# BoostConverter.net
KiCad netlist of a schematic drawn in Altium Designer
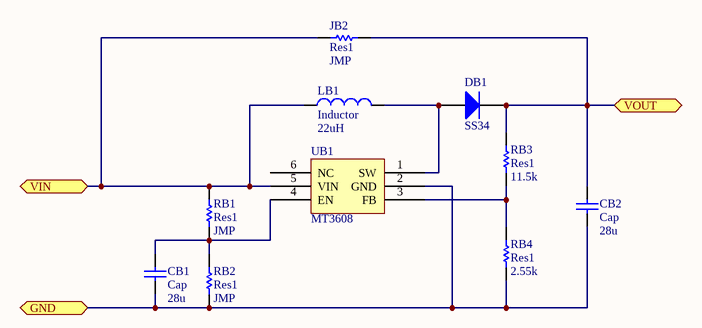
[diagram p0: BoostConverter.SchDoc]

(export (version "E")
  (design (tool "Eeschema 10.0.6"))
  (components
    (comp (ref "CB1")
      (value "Cap")
      (footprint "CAP0603R")
      (description "Capacitor")
      (fields (field (name "ALTIUM_VALUE") "28u") (field (name "PUBLISHER") "Altium Limited"))
      (libsource (lib "Standard") (part "Cap"))
    )
    (comp (ref "CB2")
      (value "Cap")
      (footprint "CAP0603R")
      (description "Capacitor")
      (fields (field (name "ALTIUM_VALUE") "28u") (field (name "PUBLISHER") "Altium Limited"))
      (libsource (lib "Standard") (part "Cap"))
    )
    (comp (ref "DB1")
      (value "SS34")
      (footprint "DO-214AC")
      (description "Default Diode")
      (fields (field (name "PUBLISHER") "Altium Limited"))
      (libsource (lib "Miscellaneous Devices") (part "Diode"))
    )
    (comp (ref "JB2")
      (value "Res1")
      (footprint "RES0603R")
      (description "Resistor")
      (fields (field (name "ALTIUM_VALUE") "JMP") (field (name "PUBLISHER") "Altium Limited"))
      (libsource (lib "Miscellaneous Devices") (part "Res1"))
    )
    (comp (ref "LB1")
      (value "Inductor")
      (footprint "INDUCTOR CD54")
      (fields (field (name "ALTIUM_VALUE") "22uH") (field (name "PUBLISHER") "Altium Limited"))
      (libsource (lib "Standard") (part "Inductor"))
    )
    (comp (ref "RB1")
      (value "Res1")
      (footprint "RES0603R")
      (description "Resistor")
      (fields (field (name "ALTIUM_VALUE") "JMP") (field (name "PUBLISHER") "Altium Limited"))
      (libsource (lib "Miscellaneous Devices") (part "Res1"))
    )
    (comp (ref "RB2")
      (value "Res1")
      (footprint "RES0603R")
      (description "Resistor")
      (fields (field (name "ALTIUM_VALUE") "JMP") (field (name "PUBLISHER") "Altium Limited"))
      (libsource (lib "Miscellaneous Devices") (part "Res1"))
    )
    (comp (ref "RB3")
      (value "Res1")
      (footprint "RES0603R")
      (description "Resistor")
      (fields (field (name "ALTIUM_VALUE") "11.5k") (field (name "PUBLISHER") "Altium Limited"))
      (libsource (lib "Miscellaneous Devices") (part "Res1"))
    )
    (comp (ref "RB4")
      (value "Res1")
      (footprint "RES0603R")
      (description "Resistor")
      (fields (field (name "ALTIUM_VALUE") "2.55k") (field (name "PUBLISHER") "Altium Limited"))
      (libsource (lib "Miscellaneous Devices") (part "Res1"))
    )
    (comp (ref "UB1")
      (value "MT3608")
      (footprint "SOT23-6")
      (description "Boost converter")
      (libsource (lib "IC") (part "MT3608"))
    )
  )
  (nets
    (net (code "1") (name "/GND") (class "Default")
      (node (ref "CB1") (pin "1") (pinfunction "1_1") (pintype "passive"))
      (node (ref "CB2") (pin "1") (pinfunction "1_1") (pintype "passive"))
      (node (ref "RB2") (pin "2") (pinfunction "2_2") (pintype "passive"))
      (node (ref "RB4") (pin "2") (pinfunction "2_2") (pintype "passive"))
      (node (ref "UB1") (pin "2") (pinfunction "GND_2") (pintype "passive"))
    )
    (net (code "2") (name "/VIN") (class "Default")
      (node (ref "JB2") (pin "1") (pinfunction "1_1") (pintype "passive"))
      (node (ref "LB1") (pin "1") (pinfunction "1_1") (pintype "passive"))
      (node (ref "RB1") (pin "1") (pinfunction "1_1") (pintype "passive"))
      (node (ref "UB1") (pin "5") (pinfunction "VIN_5") (pintype "passive"))
    )
    (net (code "3") (name "/VOUT") (class "Default")
      (node (ref "CB2") (pin "2") (pinfunction "2_2") (pintype "passive"))
      (node (ref "DB1") (pin "2") (pinfunction "K_2") (pintype "passive"))
      (node (ref "JB2") (pin "2") (pinfunction "2_2") (pintype "passive"))
      (node (ref "RB3") (pin "1") (pinfunction "1_1") (pintype "passive"))
    )
    (net (code "4") (name "Net-(DB1-A)") (class "Default")
      (node (ref "DB1") (pin "1") (pinfunction "A_1") (pintype "passive"))
      (node (ref "LB1") (pin "2") (pinfunction "2_2") (pintype "passive"))
      (node (ref "UB1") (pin "1") (pinfunction "SW_1") (pintype "passive"))
    )
    (net (code "5") (name "Net-(UB1-EN)") (class "Default")
      (node (ref "CB1") (pin "2") (pinfunction "2_2") (pintype "passive"))
      (node (ref "RB1") (pin "2") (pinfunction "2_2") (pintype "passive"))
      (node (ref "RB2") (pin "1") (pinfunction "1_1") (pintype "passive"))
      (node (ref "UB1") (pin "4") (pinfunction "EN_4") (pintype "passive"))
    )
    (net (code "6") (name "Net-(UB1-FB)") (class "Default")
      (node (ref "RB3") (pin "2") (pinfunction "2_2") (pintype "passive"))
      (node (ref "RB4") (pin "1") (pinfunction "1_1") (pintype "passive"))
      (node (ref "UB1") (pin "3") (pinfunction "FB_3") (pintype "passive"))
    )
    (net (code "7") (name "unconnected-(UB1-NC-Pad6)") (class "Default")
      (node (ref "UB1") (pin "6") (pinfunction "NC_6") (pintype "passive"))
    )
  )
)
